# ProPrj___2024-08-31.net
KiCad netlist of a schematic drawn in EasyEDA Pro
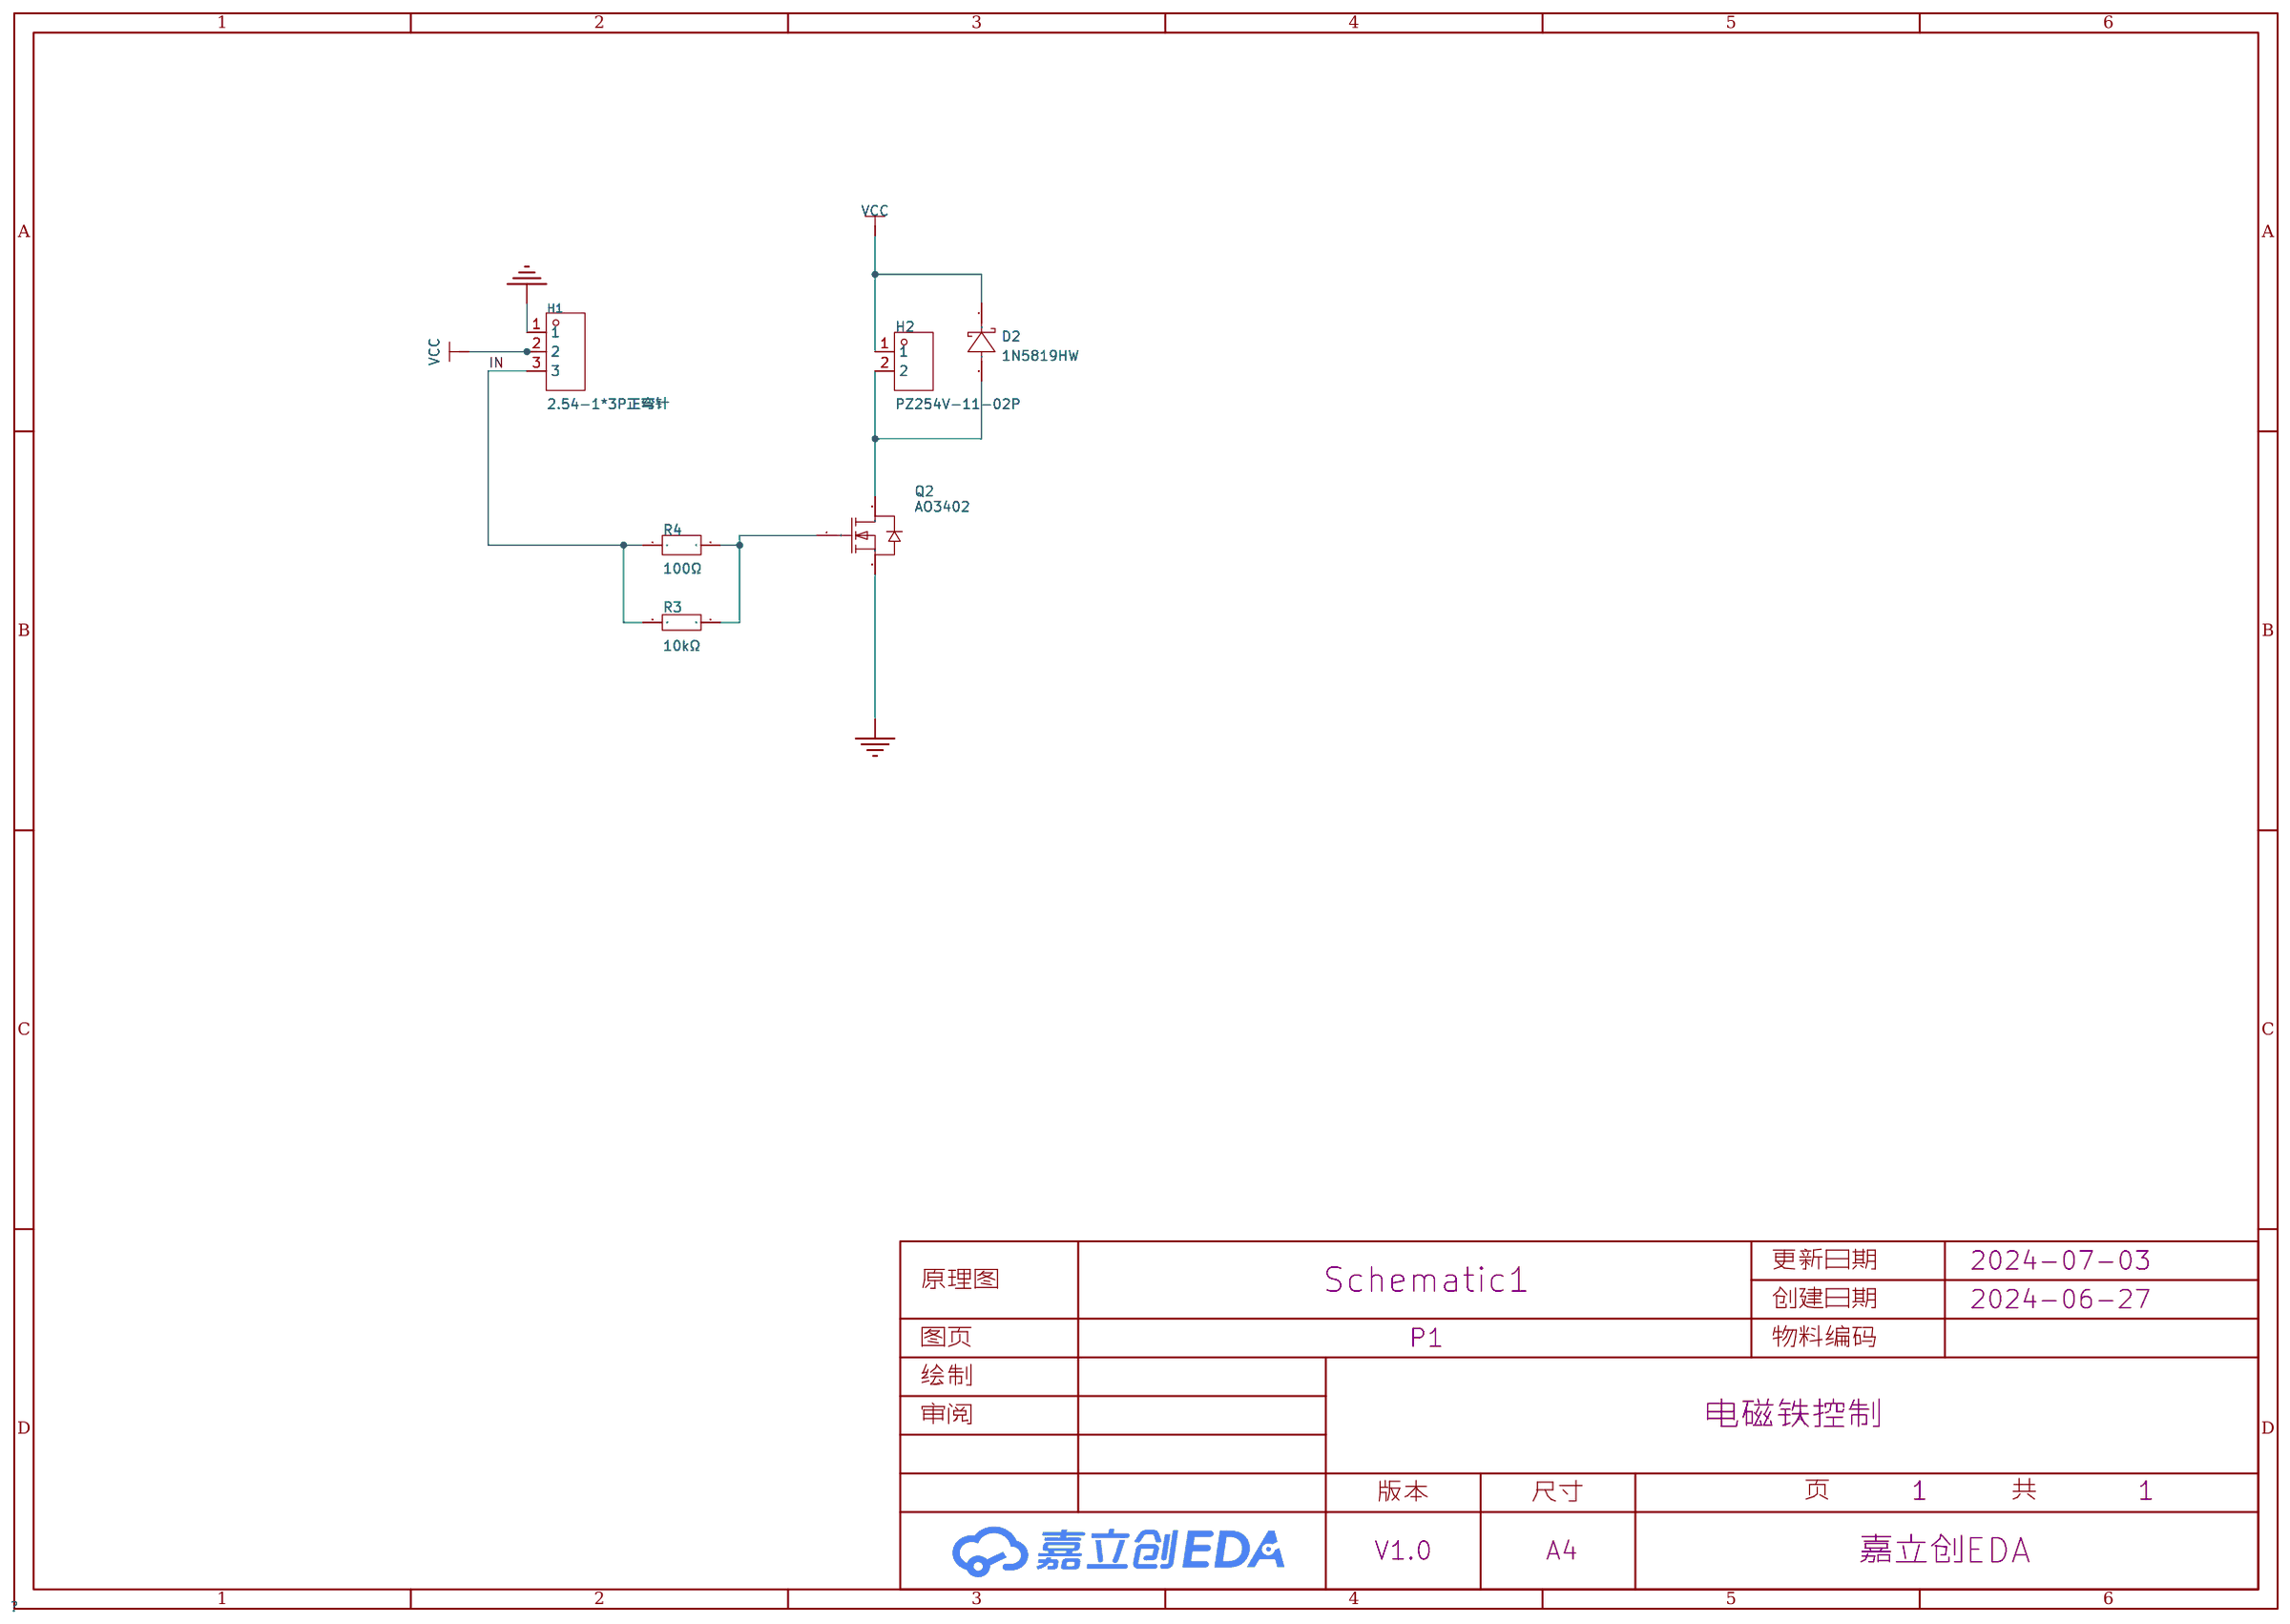
[diagram p0: schematic sheet]

(export (version "E")
  (design (tool "Eeschema 10.0.6"))
  (components
    (comp (ref "D2")
      (value "1N5819HW")
      (footprint "easyedapro:SOD-123_L2.7-W1.6-LS3.7-RD-1")
      (description "二极管配置:-;正向压降(Vf):900mV@3A;直流反向耐压(Vr):40V;平均整流电流(Io):1A;")
      (fields (field (name "Manufacturer") "TECH PUBLIC(台舟)"))
      (libsource (lib "easyedapro") (part "1N5819HW"))
    )
    (comp (ref "H1")
      (value "2.54-1*3P正弯针")
      (footprint "easyedapro:HDR-TH_3P-P2.54-H-M-BW7.2-P")
      (fields (field (name "Manufacturer") "BOOMELE(博穆精密)"))
      (libsource (lib "easyedapro") (part "C92159"))
    )
    (comp (ref "H2")
      (value "PZ254V-11-02P")
      (footprint "easyedapro:HDR-TH_2P-P2.54-V-M")
      (fields (field (name "Manufacturer") "XFCN(兴飞)"))
      (libsource (lib "easyedapro") (part "PZ254V-11-02P"))
    )
    (comp (ref "Q2")
      (value "AO3402")
      (footprint "easyedapro:SOT-23_L2.9-W1.3-P1.90-LS2.4-BR")
      (fields (field (name "Manufacturer") "AOS"))
      (libsource (lib "easyedapro") (part "AO3402_C14385"))
    )
    (comp (ref "R3")
      (value "10kΩ")
      (footprint "easyedapro:R0603")
      (description "电阻类型:厚膜电阻;阻值:10kΩ;精度:±1%;功率:100mW;最大工作电压:75V;温度系数:±100ppm/°C;")
      (fields
        (field (name "Manufacturer Part") "0603WAF1002T5E")
        (field (name "Manufacturer") "UNI-ROYAL(厚声)")
      )
      (libsource (lib "easyedapro") (part "0603WAF1002T5E"))
    )
    (comp (ref "R4")
      (value "100Ω")
      (footprint "easyedapro:R0603")
      (description "电阻类型:薄膜电阻;阻值:100Ω;精度:±0.05%;功率:100mW;最大工作电压:75V;温度系数:±5ppm/°C;")
      (fields
        (field (name "Manufacturer Part") "TNPU0603100RAZEN00")
        (field (name "Manufacturer") "VISHAY(威世)")
      )
      (libsource (lib "easyedapro") (part "TNPU0603100RAZEN00"))
    )
  )
  (nets
    (net (code "1") (name "/IN") (class "Default")
      (node (ref "H1") (pin "3") (pinfunction "3_3") (pintype "input"))
      (node (ref "R3") (pin "2") (pinfunction "2_2") (pintype "input"))
      (node (ref "R4") (pin "1") (pinfunction "1_1") (pintype "input"))
    )
    (net (code "2") (name "GND") (class "Default")
      (node (ref "H1") (pin "1") (pinfunction "1_1") (pintype "input"))
      (node (ref "Q2") (pin "2") (pinfunction "S_2") (pintype "unspecified"))
    )
    (net (code "3") (name "Net-(D2-A)") (class "Default")
      (node (ref "D2") (pin "2") (pinfunction "A_2") (pintype "input"))
      (node (ref "H2") (pin "2") (pinfunction "2_2") (pintype "unspecified"))
      (node (ref "Q2") (pin "3") (pinfunction "D_3") (pintype "unspecified"))
    )
    (net (code "4") (name "Net-(Q2-G)") (class "Default")
      (node (ref "Q2") (pin "1") (pinfunction "G_1") (pintype "unspecified"))
      (node (ref "R3") (pin "1") (pinfunction "1_1") (pintype "input"))
      (node (ref "R4") (pin "2") (pinfunction "2_2") (pintype "input"))
    )
    (net (code "5") (name "VCC") (class "Default")
      (node (ref "D2") (pin "1") (pinfunction "K_1") (pintype "input"))
      (node (ref "H1") (pin "2") (pinfunction "2_2") (pintype "input"))
      (node (ref "H2") (pin "1") (pinfunction "1_1") (pintype "unspecified"))
    )
  )
)
